# Amp_schem.net
KiCad netlist of a schematic drawn in Altium Designer
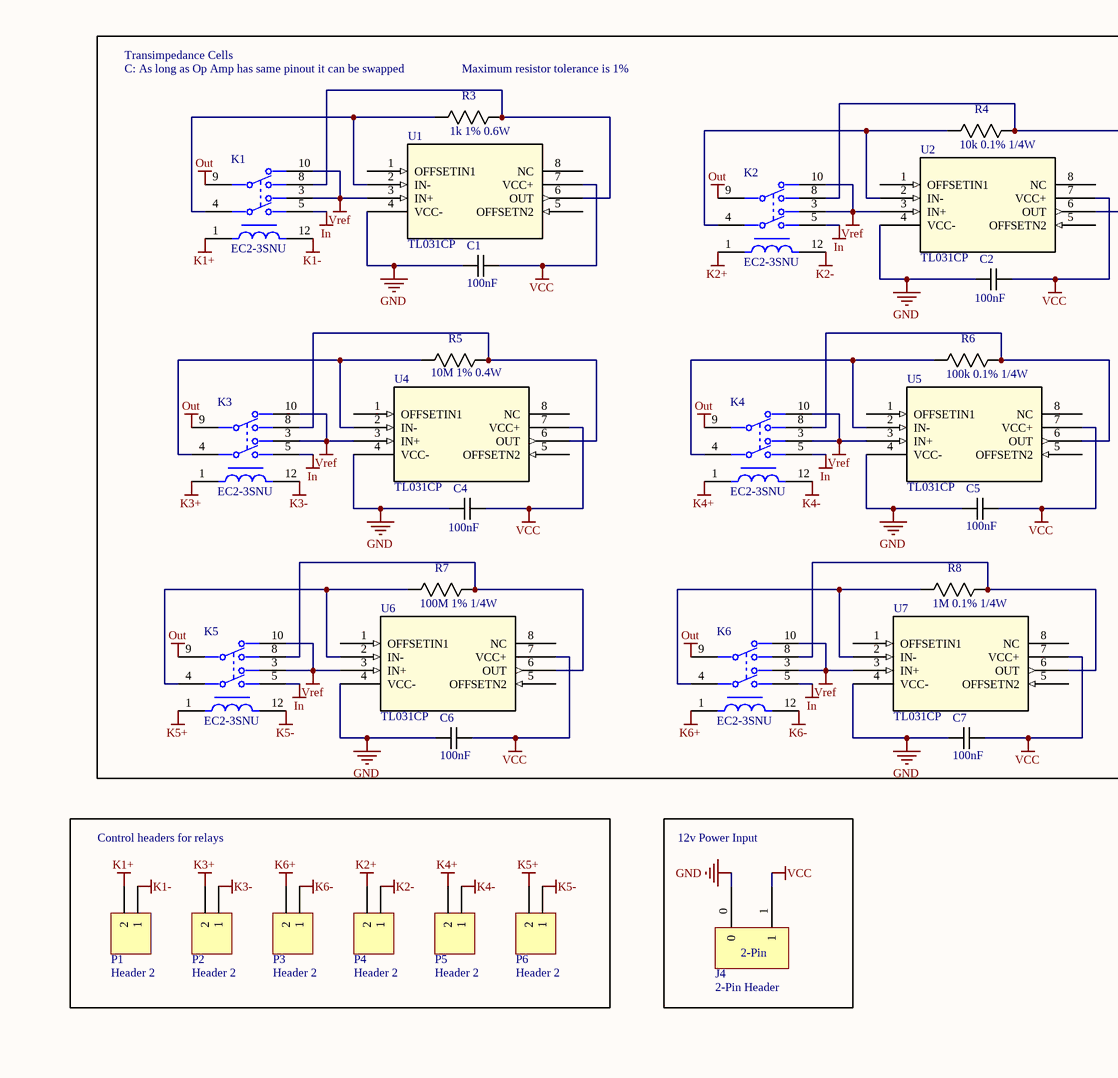
[diagram p0: Amp_schem.SchDoc, top left]
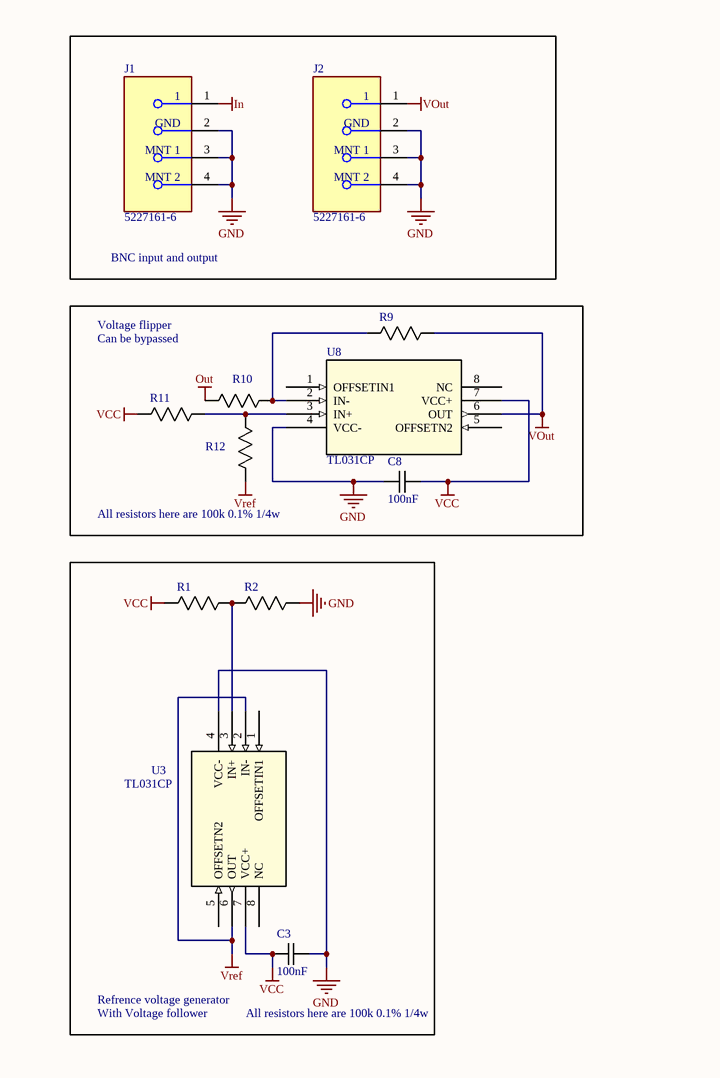
[diagram p1: Amp_schem.SchDoc, top right]
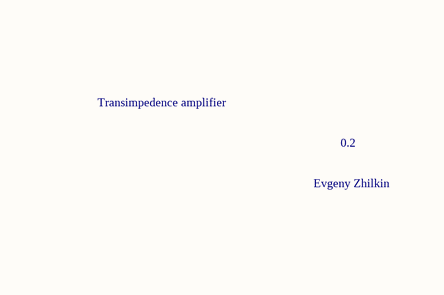
[diagram p2: Amp_schem.SchDoc, bottom right]

(export (version "E")
  (design (tool "Eeschema 10.0.6"))
  (components
    (comp (ref "C1") (value "100nF") (footprint "Resistor 1/4") (libsource (lib "TransAmpLibs") (part "Cap")))
    (comp (ref "C2") (value "100nF") (footprint "Resistor 1/4") (libsource (lib "TransAmpLibs") (part "Cap")))
    (comp (ref "C3") (value "100nF") (footprint "Resistor 1/4") (libsource (lib "TransAmpLibs") (part "Cap")))
    (comp (ref "C4") (value "100nF") (footprint "Resistor 1/4") (libsource (lib "TransAmpLibs") (part "Cap")))
    (comp (ref "C5") (value "100nF") (footprint "Resistor 1/4") (libsource (lib "TransAmpLibs") (part "Cap")))
    (comp (ref "C6") (value "100nF") (footprint "Resistor 1/4") (libsource (lib "TransAmpLibs") (part "Cap")))
    (comp (ref "C7") (value "100nF") (footprint "Resistor 1/4") (libsource (lib "TransAmpLibs") (part "Cap")))
    (comp (ref "C8") (value "100nF") (footprint "Resistor 1/4") (libsource (lib "TransAmpLibs") (part "Cap")))
    (comp (ref "J1")
      (value "5227161-6")
      (footprint "FP-5227161-6-MFG")
      (description "5227161-6 RF Connector, BNC, Jack, 50 Ohm, Right Angle PCB Mount, Commecial Grade")
      (libsource (lib "Components - 15.09.24 - 21.31") (part "CMP-03790-39546762-1"))
    )
    (comp (ref "J2")
      (value "5227161-6")
      (footprint "FP-5227161-6-MFG")
      (description "5227161-6 RF Connector, BNC, Jack, 50 Ohm, Right Angle PCB Mount, Commecial Grade")
      (libsource (lib "Components - 15.09.24 - 21.31") (part "CMP-03790-39546762-1"))
    )
    (comp (ref "J4")
      (value "2-Pin Header")
      (footprint "HDR1X2")
      (libsource (lib "TransAmpLibs") (part "2-Pin Header"))
    )
    (comp (ref "K1") (value "EC2-3SNU") (footprint "Relay") (libsource (lib "TransAmpLibs") (part "Relay")))
    (comp (ref "K2") (value "EC2-3SNU") (footprint "Relay") (libsource (lib "TransAmpLibs") (part "Relay")))
    (comp (ref "K3") (value "EC2-3SNU") (footprint "Relay") (libsource (lib "TransAmpLibs") (part "Relay")))
    (comp (ref "K4") (value "EC2-3SNU") (footprint "Relay") (libsource (lib "TransAmpLibs") (part "Relay")))
    (comp (ref "K5") (value "EC2-3SNU") (footprint "Relay") (libsource (lib "TransAmpLibs") (part "Relay")))
    (comp (ref "K6") (value "EC2-3SNU") (footprint "Relay") (libsource (lib "TransAmpLibs") (part "Relay")))
    (comp (ref "P1")
      (value "Header 2")
      (footprint "HDR1X2")
      (description "Header, 2-Pin")
      (fields (field (name "PUBLISHER") "Altium Limited"))
      (libsource (lib "Miscellaneous Connectors") (part "Header 2"))
    )
    (comp (ref "P2")
      (value "Header 2")
      (footprint "HDR1X2")
      (description "Header, 2-Pin")
      (fields (field (name "PUBLISHER") "Altium Limited"))
      (libsource (lib "Miscellaneous Connectors") (part "Header 2"))
    )
    (comp (ref "P3")
      (value "Header 2")
      (footprint "HDR1X2")
      (description "Header, 2-Pin")
      (fields (field (name "PUBLISHER") "Altium Limited"))
      (libsource (lib "Miscellaneous Connectors") (part "Header 2"))
    )
    (comp (ref "P4")
      (value "Header 2")
      (footprint "HDR1X2")
      (description "Header, 2-Pin")
      (fields (field (name "PUBLISHER") "Altium Limited"))
      (libsource (lib "Miscellaneous Connectors") (part "Header 2"))
    )
    (comp (ref "P5")
      (value "Header 2")
      (footprint "HDR1X2")
      (description "Header, 2-Pin")
      (fields (field (name "PUBLISHER") "Altium Limited"))
      (libsource (lib "Miscellaneous Connectors") (part "Header 2"))
    )
    (comp (ref "P6")
      (value "Header 2")
      (footprint "HDR1X2")
      (description "Header, 2-Pin")
      (fields (field (name "PUBLISHER") "Altium Limited"))
      (libsource (lib "Miscellaneous Connectors") (part "Header 2"))
    )
    (comp (ref "R1")
      (value "100k 0.1% 1/4w")
      (footprint "Resistor 0.4W")
      (libsource (lib "TransAmpLibs") (part "Resistor 1/4W"))
    )
    (comp (ref "R2")
      (value "100k 0.1% 1/4w")
      (footprint "Resistor 0.4W")
      (libsource (lib "TransAmpLibs") (part "Resistor 1/4W"))
    )
    (comp (ref "R3")
      (value "1k 1% 0.6W")
      (footprint "Resistor 0.4W")
      (libsource (lib "TransAmpLibs") (part "Resistor 1/4W"))
    )
    (comp (ref "R4")
      (value "10k 0.1% 1/4W")
      (footprint "Resistor 0.4W")
      (libsource (lib "TransAmpLibs") (part "Resistor 1/4W"))
    )
    (comp (ref "R5")
      (value "10M 1% 0.4W")
      (footprint "Resistor 0.4W")
      (libsource (lib "TransAmpLibs") (part "Resistor 1/4W"))
    )
    (comp (ref "R6")
      (value "100k 0.1% 1/4W")
      (footprint "Resistor 0.4W")
      (libsource (lib "TransAmpLibs") (part "Resistor 1/4W"))
    )
    (comp (ref "R7")
      (value "100M 1% 1/4W")
      (footprint "Resistor 0.4W")
      (libsource (lib "TransAmpLibs") (part "Resistor 1/4W"))
    )
    (comp (ref "R8")
      (value "1M 0.1% 1/4W")
      (footprint "Resistor 0.4W")
      (libsource (lib "TransAmpLibs") (part "Resistor 1/4W"))
    )
    (comp (ref "R9")
      (value "100k 0.1% 1/4w")
      (footprint "Resistor 0.4W")
      (libsource (lib "TransAmpLibs") (part "Resistor 1/4W"))
    )
    (comp (ref "R10")
      (value "100k 0.1% 1/4w")
      (footprint "Resistor 0.4W")
      (libsource (lib "TransAmpLibs") (part "Resistor 1/4W"))
    )
    (comp (ref "R11")
      (value "100k 0.1% 1/4w")
      (footprint "Resistor 0.4W")
      (libsource (lib "TransAmpLibs") (part "Resistor 1/4W"))
    )
    (comp (ref "R12")
      (value "100k 0.1% 1/4w")
      (footprint "Resistor 0.4W")
      (libsource (lib "TransAmpLibs") (part "Resistor 1/4W"))
    )
    (comp (ref "U1")
      (value "TL031CP")
      (footprint "P8")
      (description "No Description Available")
      (libsource (lib "") (part "TL031CP_1"))
    )
    (comp (ref "U2")
      (value "TL031CP")
      (footprint "P8")
      (description "No Description Available")
      (libsource (lib "") (part "TL031CP_1"))
    )
    (comp (ref "U3")
      (value "TL031CP")
      (footprint "P8")
      (description "No Description Available")
      (libsource (lib "TL031CP") (part "TL031CP"))
    )
    (comp (ref "U4")
      (value "TL031CP")
      (footprint "P8")
      (description "No Description Available")
      (libsource (lib "") (part "TL031CP_1"))
    )
    (comp (ref "U5")
      (value "TL031CP")
      (footprint "P8")
      (description "No Description Available")
      (libsource (lib "") (part "TL031CP_1"))
    )
    (comp (ref "U6")
      (value "TL031CP")
      (footprint "P8")
      (description "No Description Available")
      (libsource (lib "") (part "TL031CP_1"))
    )
    (comp (ref "U7")
      (value "TL031CP")
      (footprint "P8")
      (description "No Description Available")
      (libsource (lib "") (part "TL031CP_1"))
    )
    (comp (ref "U8")
      (value "TL031CP")
      (footprint "P8")
      (description "No Description Available")
      (libsource (lib "") (part "TL031CP_1"))
    )
  )
  (nets
    (net (code "1") (name "GND") (class "Default")
      (node (ref "C1") (pin "1") (pinfunction "1_1") (pintype "passive"))
      (node (ref "C2") (pin "1") (pinfunction "1_1") (pintype "passive"))
      (node (ref "C3") (pin "2") (pinfunction "2_2") (pintype "passive"))
      (node (ref "C4") (pin "1") (pinfunction "1_1") (pintype "passive"))
      (node (ref "C5") (pin "1") (pinfunction "1_1") (pintype "passive"))
      (node (ref "C6") (pin "1") (pinfunction "1_1") (pintype "passive"))
      (node (ref "C7") (pin "1") (pinfunction "1_1") (pintype "passive"))
      (node (ref "C8") (pin "1") (pinfunction "1_1") (pintype "passive"))
      (node (ref "J1") (pin "2") (pinfunction "GND_2") (pintype "passive"))
      (node (ref "J1") (pin "3") (pinfunction "MNT_1_3") (pintype "passive"))
      (node (ref "J1") (pin "4") (pinfunction "MNT_2_4") (pintype "passive"))
      (node (ref "J2") (pin "2") (pinfunction "GND_2") (pintype "passive"))
      (node (ref "J2") (pin "3") (pinfunction "MNT_1_3") (pintype "passive"))
      (node (ref "J2") (pin "4") (pinfunction "MNT_2_4") (pintype "passive"))
      (node (ref "J4") (pin "0") (pinfunction "0_0") (pintype "passive"))
      (node (ref "R2") (pin "2") (pinfunction "2_2") (pintype "passive"))
      (node (ref "U1") (pin "4") (pinfunction "VCC-_4") (pintype "power_in"))
      (node (ref "U2") (pin "4") (pinfunction "VCC-_4") (pintype "power_in"))
      (node (ref "U3") (pin "4") (pinfunction "VCC-_4") (pintype "power_in"))
      (node (ref "U4") (pin "4") (pinfunction "VCC-_4") (pintype "power_in"))
      (node (ref "U5") (pin "4") (pinfunction "VCC-_4") (pintype "power_in"))
      (node (ref "U6") (pin "4") (pinfunction "VCC-_4") (pintype "power_in"))
      (node (ref "U7") (pin "4") (pinfunction "VCC-_4") (pintype "power_in"))
      (node (ref "U8") (pin "4") (pinfunction "VCC-_4") (pintype "power_in"))
    )
    (net (code "2") (name "In") (class "Default")
      (node (ref "J1") (pin "1") (pinfunction "1_1") (pintype "passive"))
      (node (ref "K1") (pin "5") (pinfunction "5_5") (pintype "passive"))
      (node (ref "K2") (pin "5") (pinfunction "5_5") (pintype "passive"))
      (node (ref "K3") (pin "5") (pinfunction "5_5") (pintype "passive"))
      (node (ref "K4") (pin "5") (pinfunction "5_5") (pintype "passive"))
      (node (ref "K5") (pin "5") (pinfunction "5_5") (pintype "passive"))
      (node (ref "K6") (pin "5") (pinfunction "5_5") (pintype "passive"))
    )
    (net (code "3") (name "K1+") (class "Default")
      (node (ref "K1") (pin "1") (pinfunction "1_1") (pintype "passive"))
      (node (ref "P1") (pin "2") (pinfunction "2_2") (pintype "passive"))
    )
    (net (code "4") (name "K1-") (class "Default")
      (node (ref "K1") (pin "12") (pinfunction "12_12") (pintype "passive"))
      (node (ref "P1") (pin "1") (pinfunction "1_1") (pintype "passive"))
    )
    (net (code "5") (name "K2+") (class "Default")
      (node (ref "K2") (pin "1") (pinfunction "1_1") (pintype "passive"))
      (node (ref "P4") (pin "2") (pinfunction "2_2") (pintype "passive"))
    )
    (net (code "6") (name "K2-") (class "Default")
      (node (ref "K2") (pin "12") (pinfunction "12_12") (pintype "passive"))
      (node (ref "P4") (pin "1") (pinfunction "1_1") (pintype "passive"))
    )
    (net (code "7") (name "K3+") (class "Default")
      (node (ref "K3") (pin "1") (pinfunction "1_1") (pintype "passive"))
      (node (ref "P2") (pin "2") (pinfunction "2_2") (pintype "passive"))
    )
    (net (code "8") (name "K3-") (class "Default")
      (node (ref "K3") (pin "12") (pinfunction "12_12") (pintype "passive"))
      (node (ref "P2") (pin "1") (pinfunction "1_1") (pintype "passive"))
    )
    (net (code "9") (name "K4+") (class "Default")
      (node (ref "K4") (pin "1") (pinfunction "1_1") (pintype "passive"))
      (node (ref "P5") (pin "2") (pinfunction "2_2") (pintype "passive"))
    )
    (net (code "10") (name "K4-") (class "Default")
      (node (ref "K4") (pin "12") (pinfunction "12_12") (pintype "passive"))
      (node (ref "P5") (pin "1") (pinfunction "1_1") (pintype "passive"))
    )
    (net (code "11") (name "K5+") (class "Default")
      (node (ref "K5") (pin "1") (pinfunction "1_1") (pintype "passive"))
      (node (ref "P6") (pin "2") (pinfunction "2_2") (pintype "passive"))
    )
    (net (code "12") (name "K5-") (class "Default")
      (node (ref "K5") (pin "12") (pinfunction "12_12") (pintype "passive"))
      (node (ref "P6") (pin "1") (pinfunction "1_1") (pintype "passive"))
    )
    (net (code "13") (name "K6+") (class "Default")
      (node (ref "K6") (pin "1") (pinfunction "1_1") (pintype "passive"))
      (node (ref "P3") (pin "2") (pinfunction "2_2") (pintype "passive"))
    )
    (net (code "14") (name "K6-") (class "Default")
      (node (ref "K6") (pin "12") (pinfunction "12_12") (pintype "passive"))
      (node (ref "P3") (pin "1") (pinfunction "1_1") (pintype "passive"))
    )
    (net (code "15") (name "Net-(U1-IN-)") (class "Default")
      (node (ref "K1") (pin "4") (pinfunction "4_4") (pintype "passive"))
      (node (ref "R3") (pin "1") (pinfunction "1_1") (pintype "passive"))
      (node (ref "U1") (pin "2") (pinfunction "IN-_2") (pintype "input"))
    )
    (net (code "16") (name "Net-(U1-OUT)") (class "Default")
      (node (ref "K1") (pin "8") (pinfunction "8_8") (pintype "passive"))
      (node (ref "R3") (pin "2") (pinfunction "2_2") (pintype "passive"))
      (node (ref "U1") (pin "6") (pinfunction "OUT_6") (pintype "output"))
    )
    (net (code "17") (name "Net-(U2-IN-)") (class "Default")
      (node (ref "K2") (pin "4") (pinfunction "4_4") (pintype "passive"))
      (node (ref "R4") (pin "1") (pinfunction "1_1") (pintype "passive"))
      (node (ref "U2") (pin "2") (pinfunction "IN-_2") (pintype "input"))
    )
    (net (code "18") (name "Net-(U2-OUT)") (class "Default")
      (node (ref "K2") (pin "8") (pinfunction "8_8") (pintype "passive"))
      (node (ref "R4") (pin "2") (pinfunction "2_2") (pintype "passive"))
      (node (ref "U2") (pin "6") (pinfunction "OUT_6") (pintype "output"))
    )
    (net (code "19") (name "Net-(U3-IN+)") (class "Default")
      (node (ref "R1") (pin "2") (pinfunction "2_2") (pintype "passive"))
      (node (ref "R2") (pin "1") (pinfunction "1_1") (pintype "passive"))
      (node (ref "U3") (pin "3") (pinfunction "IN+_3") (pintype "input"))
    )
    (net (code "20") (name "Net-(U4-IN-)") (class "Default")
      (node (ref "K3") (pin "4") (pinfunction "4_4") (pintype "passive"))
      (node (ref "R5") (pin "1") (pinfunction "1_1") (pintype "passive"))
      (node (ref "U4") (pin "2") (pinfunction "IN-_2") (pintype "input"))
    )
    (net (code "21") (name "Net-(U4-OUT)") (class "Default")
      (node (ref "K3") (pin "8") (pinfunction "8_8") (pintype "passive"))
      (node (ref "R5") (pin "2") (pinfunction "2_2") (pintype "passive"))
      (node (ref "U4") (pin "6") (pinfunction "OUT_6") (pintype "output"))
    )
    (net (code "22") (name "Net-(U5-IN-)") (class "Default")
      (node (ref "K4") (pin "4") (pinfunction "4_4") (pintype "passive"))
      (node (ref "R6") (pin "1") (pinfunction "1_1") (pintype "passive"))
      (node (ref "U5") (pin "2") (pinfunction "IN-_2") (pintype "input"))
    )
    (net (code "23") (name "Net-(U5-OUT)") (class "Default")
      (node (ref "K4") (pin "8") (pinfunction "8_8") (pintype "passive"))
      (node (ref "R6") (pin "2") (pinfunction "2_2") (pintype "passive"))
      (node (ref "U5") (pin "6") (pinfunction "OUT_6") (pintype "output"))
    )
    (net (code "24") (name "Net-(U6-IN-)") (class "Default")
      (node (ref "K5") (pin "4") (pinfunction "4_4") (pintype "passive"))
      (node (ref "R7") (pin "1") (pinfunction "1_1") (pintype "passive"))
      (node (ref "U6") (pin "2") (pinfunction "IN-_2") (pintype "input"))
    )
    (net (code "25") (name "Net-(U6-OUT)") (class "Default")
      (node (ref "K5") (pin "8") (pinfunction "8_8") (pintype "passive"))
      (node (ref "R7") (pin "2") (pinfunction "2_2") (pintype "passive"))
      (node (ref "U6") (pin "6") (pinfunction "OUT_6") (pintype "output"))
    )
    (net (code "26") (name "Net-(U7-IN-)") (class "Default")
      (node (ref "K6") (pin "4") (pinfunction "4_4") (pintype "passive"))
      (node (ref "R8") (pin "1") (pinfunction "1_1") (pintype "passive"))
      (node (ref "U7") (pin "2") (pinfunction "IN-_2") (pintype "input"))
    )
    (net (code "27") (name "Net-(U7-OUT)") (class "Default")
      (node (ref "K6") (pin "8") (pinfunction "8_8") (pintype "passive"))
      (node (ref "R8") (pin "2") (pinfunction "2_2") (pintype "passive"))
      (node (ref "U7") (pin "6") (pinfunction "OUT_6") (pintype "output"))
    )
    (net (code "28") (name "Net-(U8-IN+)") (class "Default")
      (node (ref "R11") (pin "2") (pinfunction "2_2") (pintype "passive"))
      (node (ref "R12") (pin "2") (pinfunction "2_2") (pintype "passive"))
      (node (ref "U8") (pin "3") (pinfunction "IN+_3") (pintype "input"))
    )
    (net (code "29") (name "Net-(U8-IN-)") (class "Default")
      (node (ref "R10") (pin "2") (pinfunction "2_2") (pintype "passive"))
      (node (ref "R9") (pin "1") (pinfunction "1_1") (pintype "passive"))
      (node (ref "U8") (pin "2") (pinfunction "IN-_2") (pintype "input"))
    )
    (net (code "30") (name "Out") (class "Default")
      (node (ref "K1") (pin "9") (pinfunction "9_9") (pintype "passive"))
      (node (ref "K2") (pin "9") (pinfunction "9_9") (pintype "passive"))
      (node (ref "K3") (pin "9") (pinfunction "9_9") (pintype "passive"))
      (node (ref "K4") (pin "9") (pinfunction "9_9") (pintype "passive"))
      (node (ref "K5") (pin "9") (pinfunction "9_9") (pintype "passive"))
      (node (ref "K6") (pin "9") (pinfunction "9_9") (pintype "passive"))
      (node (ref "R10") (pin "1") (pinfunction "1_1") (pintype "passive"))
    )
    (net (code "31") (name "VCC") (class "Default")
      (node (ref "C1") (pin "2") (pinfunction "2_2") (pintype "passive"))
      (node (ref "C2") (pin "2") (pinfunction "2_2") (pintype "passive"))
      (node (ref "C3") (pin "1") (pinfunction "1_1") (pintype "passive"))
      (node (ref "C4") (pin "2") (pinfunction "2_2") (pintype "passive"))
      (node (ref "C5") (pin "2") (pinfunction "2_2") (pintype "passive"))
      (node (ref "C6") (pin "2") (pinfunction "2_2") (pintype "passive"))
      (node (ref "C7") (pin "2") (pinfunction "2_2") (pintype "passive"))
      (node (ref "C8") (pin "2") (pinfunction "2_2") (pintype "passive"))
      (node (ref "J4") (pin "1") (pinfunction "1_1") (pintype "passive"))
      (node (ref "R1") (pin "1") (pinfunction "1_1") (pintype "passive"))
      (node (ref "R11") (pin "1") (pinfunction "1_1") (pintype "passive"))
      (node (ref "U1") (pin "7") (pinfunction "VCC+_7") (pintype "power_in"))
      (node (ref "U2") (pin "7") (pinfunction "VCC+_7") (pintype "power_in"))
      (node (ref "U3") (pin "7") (pinfunction "VCC+_7") (pintype "power_in"))
      (node (ref "U4") (pin "7") (pinfunction "VCC+_7") (pintype "power_in"))
      (node (ref "U5") (pin "7") (pinfunction "VCC+_7") (pintype "power_in"))
      (node (ref "U6") (pin "7") (pinfunction "VCC+_7") (pintype "power_in"))
      (node (ref "U7") (pin "7") (pinfunction "VCC+_7") (pintype "power_in"))
      (node (ref "U8") (pin "7") (pinfunction "VCC+_7") (pintype "power_in"))
    )
    (net (code "32") (name "VOut") (class "Default")
      (node (ref "J2") (pin "1") (pinfunction "1_1") (pintype "passive"))
      (node (ref "R9") (pin "2") (pinfunction "2_2") (pintype "passive"))
      (node (ref "U8") (pin "6") (pinfunction "OUT_6") (pintype "output"))
    )
    (net (code "33") (name "Vref") (class "Default")
      (node (ref "K1") (pin "10") (pinfunction "10_10") (pintype "passive"))
      (node (ref "K1") (pin "3") (pinfunction "3_3") (pintype "passive"))
      (node (ref "K2") (pin "10") (pinfunction "10_10") (pintype "passive"))
      (node (ref "K2") (pin "3") (pinfunction "3_3") (pintype "passive"))
      (node (ref "K3") (pin "10") (pinfunction "10_10") (pintype "passive"))
      (node (ref "K3") (pin "3") (pinfunction "3_3") (pintype "passive"))
      (node (ref "K4") (pin "10") (pinfunction "10_10") (pintype "passive"))
      (node (ref "K4") (pin "3") (pinfunction "3_3") (pintype "passive"))
      (node (ref "K5") (pin "10") (pinfunction "10_10") (pintype "passive"))
      (node (ref "K5") (pin "3") (pinfunction "3_3") (pintype "passive"))
      (node (ref "K6") (pin "10") (pinfunction "10_10") (pintype "passive"))
      (node (ref "K6") (pin "3") (pinfunction "3_3") (pintype "passive"))
      (node (ref "R12") (pin "1") (pinfunction "1_1") (pintype "passive"))
      (node (ref "U1") (pin "3") (pinfunction "IN+_3") (pintype "input"))
      (node (ref "U2") (pin "3") (pinfunction "IN+_3") (pintype "input"))
      (node (ref "U3") (pin "2") (pinfunction "IN-_2") (pintype "input"))
      (node (ref "U3") (pin "6") (pinfunction "OUT_6") (pintype "output"))
      (node (ref "U4") (pin "3") (pinfunction "IN+_3") (pintype "input"))
      (node (ref "U5") (pin "3") (pinfunction "IN+_3") (pintype "input"))
      (node (ref "U6") (pin "3") (pinfunction "IN+_3") (pintype "input"))
      (node (ref "U7") (pin "3") (pinfunction "IN+_3") (pintype "input"))
    )
    (net (code "34") (name "unconnected-(U1-NC-Pad8)") (class "Default")
      (node (ref "U1") (pin "8") (pinfunction "NC_8") (pintype "passive"))
    )
    (net (code "35") (name "unconnected-(U1-OFFSETIN1-Pad1)") (class "Default")
      (node (ref "U1") (pin "1") (pinfunction "OFFSETIN1_1") (pintype "input"))
    )
    (net (code "36") (name "unconnected-(U1-OFFSETN2-Pad5)") (class "Default")
      (node (ref "U1") (pin "5") (pinfunction "OFFSETN2_5") (pintype "input"))
    )
    (net (code "37") (name "unconnected-(U2-NC-Pad8)") (class "Default")
      (node (ref "U2") (pin "8") (pinfunction "NC_8") (pintype "passive"))
    )
    (net (code "38") (name "unconnected-(U2-OFFSETIN1-Pad1)") (class "Default")
      (node (ref "U2") (pin "1") (pinfunction "OFFSETIN1_1") (pintype "input"))
    )
    (net (code "39") (name "unconnected-(U2-OFFSETN2-Pad5)") (class "Default")
      (node (ref "U2") (pin "5") (pinfunction "OFFSETN2_5") (pintype "input"))
    )
    (net (code "40") (name "unconnected-(U3-NC-Pad8)") (class "Default")
      (node (ref "U3") (pin "8") (pinfunction "NC_8") (pintype "passive"))
    )
    (net (code "41") (name "unconnected-(U3-OFFSETIN1-Pad1)") (class "Default")
      (node (ref "U3") (pin "1") (pinfunction "OFFSETIN1_1") (pintype "input"))
    )
    (net (code "42") (name "unconnected-(U3-OFFSETN2-Pad5)") (class "Default")
      (node (ref "U3") (pin "5") (pinfunction "OFFSETN2_5") (pintype "input"))
    )
    (net (code "43") (name "unconnected-(U4-NC-Pad8)") (class "Default")
      (node (ref "U4") (pin "8") (pinfunction "NC_8") (pintype "passive"))
    )
    (net (code "44") (name "unconnected-(U4-OFFSETIN1-Pad1)") (class "Default")
      (node (ref "U4") (pin "1") (pinfunction "OFFSETIN1_1") (pintype "input"))
    )
    (net (code "45") (name "unconnected-(U4-OFFSETN2-Pad5)") (class "Default")
      (node (ref "U4") (pin "5") (pinfunction "OFFSETN2_5") (pintype "input"))
    )
    (net (code "46") (name "unconnected-(U5-NC-Pad8)") (class "Default")
      (node (ref "U5") (pin "8") (pinfunction "NC_8") (pintype "passive"))
    )
    (net (code "47") (name "unconnected-(U5-OFFSETIN1-Pad1)") (class "Default")
      (node (ref "U5") (pin "1") (pinfunction "OFFSETIN1_1") (pintype "input"))
    )
    (net (code "48") (name "unconnected-(U5-OFFSETN2-Pad5)") (class "Default")
      (node (ref "U5") (pin "5") (pinfunction "OFFSETN2_5") (pintype "input"))
    )
    (net (code "49") (name "unconnected-(U6-NC-Pad8)") (class "Default")
      (node (ref "U6") (pin "8") (pinfunction "NC_8") (pintype "passive"))
    )
    (net (code "50") (name "unconnected-(U6-OFFSETIN1-Pad1)") (class "Default")
      (node (ref "U6") (pin "1") (pinfunction "OFFSETIN1_1") (pintype "input"))
    )
    (net (code "51") (name "unconnected-(U6-OFFSETN2-Pad5)") (class "Default")
      (node (ref "U6") (pin "5") (pinfunction "OFFSETN2_5") (pintype "input"))
    )
    (net (code "52") (name "unconnected-(U7-NC-Pad8)") (class "Default")
      (node (ref "U7") (pin "8") (pinfunction "NC_8") (pintype "passive"))
    )
    (net (code "53") (name "unconnected-(U7-OFFSETIN1-Pad1)") (class "Default")
      (node (ref "U7") (pin "1") (pinfunction "OFFSETIN1_1") (pintype "input"))
    )
    (net (code "54") (name "unconnected-(U7-OFFSETN2-Pad5)") (class "Default")
      (node (ref "U7") (pin "5") (pinfunction "OFFSETN2_5") (pintype "input"))
    )
    (net (code "55") (name "unconnected-(U8-NC-Pad8)") (class "Default")
      (node (ref "U8") (pin "8") (pinfunction "NC_8") (pintype "passive"))
    )
    (net (code "56") (name "unconnected-(U8-OFFSETIN1-Pad1)") (class "Default")
      (node (ref "U8") (pin "1") (pinfunction "OFFSETIN1_1") (pintype "input"))
    )
    (net (code "57") (name "unconnected-(U8-OFFSETN2-Pad5)") (class "Default")
      (node (ref "U8") (pin "5") (pinfunction "OFFSETN2_5") (pintype "input"))
    )
  )
)
